# Metronome.net
KiCad netlist of a schematic drawn in Altium Designer
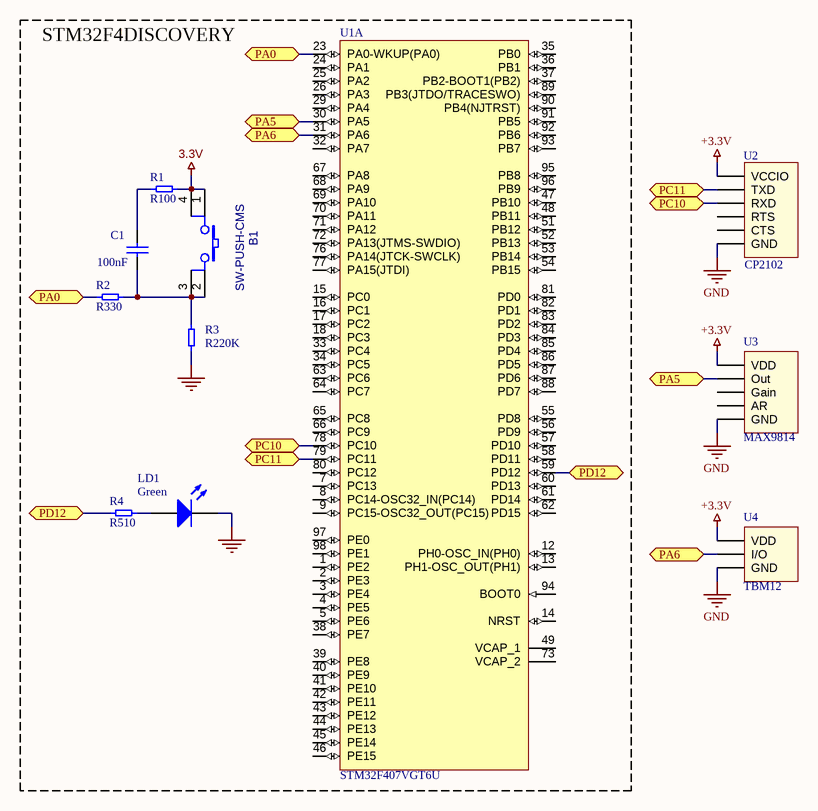
[diagram p0: Metronome.SchDoc]

(export (version "E")
  (design (tool "Eeschema 10.0.6"))
  (components
    (comp (ref "B1")
      (value "SW-PUSH-CMS")
      (footprint "BP1CMS")
      (description "Non-Open Push-Button 0.1A 24V")
      (libsource (lib "MB913_1") (part "SW-PUSH-CMS"))
    )
    (comp (ref "C1")
      (value "100nF")
      (footprint "RAD-0.3")
      (description "Capacitor")
      (fields (field (name "PUBLISHER") "Altium Limited"))
      (libsource (lib "Miscellaneous Devices") (part "Cap"))
    )
    (comp (ref "LD1")
      (value "Green")
      (footprint "3.2X1.6X1.1")
      (description "Typical RED, GREEN, YELLOW, AMBER GaAs LED")
      (fields (field (name "PUBLISHER") "Altium Limited"))
      (libsource (lib "Miscellaneous Devices") (part "LED2"))
    )
    (comp (ref "R1") (value "R100") (footprint "SMD") (libsource (lib "Metronome_components") (part "R330")))
    (comp (ref "R2") (value "R330") (footprint "SMD") (libsource (lib "Metronome_components") (part "R330")))
    (comp (ref "R3") (value "R220K") (footprint "SMD") (libsource (lib "Metronome_components") (part "R330")))
    (comp (ref "R4") (value "R510") (footprint "SMD") (libsource (lib "Metronome_components") (part "R330")))
    (comp (ref "U1")
      (value "STM32F407VGT6U")
      (footprint "STM-LQFP100_N")
      (fields (field (name "MANUFACTURER") "STMicroelectronics"))
      (libsource (lib "STMicroelectronics STM32 F4") (part "STM32F407VGT6U"))
    )
    (comp (ref "U2")
      (value "CP2102")
      (footprint "CP2102_MD")
      (description "UART-USB converter module")
      (libsource (lib "Metronome_components") (part "CP2102"))
    )
    (comp (ref "U3")
      (value "MAX9814")
      (footprint "MAX9814")
      (description "Microphone module. 3.3V - 5V. Output: 2Vpp max")
      (libsource (lib "Metronome_components") (part "MAX9814"))
    )
    (comp (ref "U4")
      (value "TBM12")
      (footprint "TBM12")
      (description "Passive buzzer. 3.3V - 5V")
      (libsource (lib "Metronome_components") (part "TBM12"))
    )
  )
  (nets
    (net (code "1") (name "+3.3V") (class "Default")
      (node (ref "U2") (pin "0") (pinfunction "VCCIO_0") (pintype "passive"))
      (node (ref "U3") (pin "0") (pinfunction "VDD_0") (pintype "power_in"))
      (node (ref "U4") (pin "0") (pinfunction "VDD_0") (pintype "power_in"))
    )
    (net (code "2") (name "/PA0") (class "Default")
      (node (ref "R2") (pin "0") (pinfunction "1_0") (pintype "passive"))
      (node (ref "U1") (pin "23") (pinfunction "PA0-WKUP(PA0)_23") (pintype "bidirectional"))
    )
    (net (code "3") (name "/PA5") (class "Default")
      (node (ref "U1") (pin "30") (pinfunction "PA5_30") (pintype "bidirectional"))
      (node (ref "U3") (pin "1") (pinfunction "Out_1") (pintype "passive"))
    )
    (net (code "4") (name "/PA6") (class "Default")
      (node (ref "U1") (pin "31") (pinfunction "PA6_31") (pintype "bidirectional"))
      (node (ref "U4") (pin "1") (pinfunction "I/O_1") (pintype "passive"))
    )
    (net (code "5") (name "/PC10") (class "Default")
      (node (ref "U1") (pin "78") (pinfunction "PC10_78") (pintype "bidirectional"))
      (node (ref "U2") (pin "2") (pinfunction "RXD_2") (pintype "passive"))
    )
    (net (code "6") (name "/PC11") (class "Default")
      (node (ref "U1") (pin "79") (pinfunction "PC11_79") (pintype "bidirectional"))
      (node (ref "U2") (pin "1") (pinfunction "TXD_1") (pintype "passive"))
    )
    (net (code "7") (name "/PD12") (class "Default")
      (node (ref "R4") (pin "0") (pinfunction "1_0") (pintype "passive"))
      (node (ref "U1") (pin "59") (pinfunction "PD12_59") (pintype "bidirectional"))
    )
    (net (code "8") (name "3.3V") (class "Default")
      (node (ref "B1") (pin "1") (pinfunction "1_1") (pintype "passive"))
      (node (ref "B1") (pin "4") (pinfunction "4_4") (pintype "passive"))
      (node (ref "R1") (pin "1") (pinfunction "2_1") (pintype "passive"))
    )
    (net (code "9") (name "GND") (class "Default")
      (node (ref "LD1") (pin "2") (pinfunction "K_2") (pintype "passive"))
      (node (ref "R3") (pin "0") (pinfunction "1_0") (pintype "passive"))
      (node (ref "U2") (pin "5") (pinfunction "GND_5") (pintype "passive"))
      (node (ref "U3") (pin "4") (pinfunction "GND_4") (pintype "passive"))
      (node (ref "U4") (pin "2") (pinfunction "GND_2") (pintype "passive"))
    )
    (net (code "10") (name "Net-(LD1-A)") (class "Default")
      (node (ref "LD1") (pin "1") (pinfunction "A_1") (pintype "passive"))
      (node (ref "R4") (pin "1") (pinfunction "2_1") (pintype "passive"))
    )
    (net (code "11") (name "Net-(R1-1)") (class "Default")
      (node (ref "C1") (pin "2") (pinfunction "2_2") (pintype "passive"))
      (node (ref "R1") (pin "0") (pinfunction "1_0") (pintype "passive"))
    )
    (net (code "12") (name "Net-(R2-2)") (class "Default")
      (node (ref "B1") (pin "2") (pinfunction "2_2") (pintype "passive"))
      (node (ref "B1") (pin "3") (pinfunction "3_3") (pintype "passive"))
      (node (ref "C1") (pin "1") (pinfunction "1_1") (pintype "passive"))
      (node (ref "R2") (pin "1") (pinfunction "2_1") (pintype "passive"))
      (node (ref "R3") (pin "1") (pinfunction "2_1") (pintype "passive"))
    )
    (net (code "13") (name "unconnected-(U1A-BOOT0-Pad94)") (class "Default")
      (node (ref "U1") (pin "94") (pinfunction "BOOT0_94") (pintype "input"))
    )
    (net (code "14") (name "unconnected-(U1A-NRST-Pad14)") (class "Default")
      (node (ref "U1") (pin "14") (pinfunction "NRST_14") (pintype "bidirectional"))
    )
    (net (code "15") (name "unconnected-(U1A-PA1-Pad24)") (class "Default")
      (node (ref "U1") (pin "24") (pinfunction "PA1_24") (pintype "bidirectional"))
    )
    (net (code "16") (name "unconnected-(U1A-PA2-Pad25)") (class "Default")
      (node (ref "U1") (pin "25") (pinfunction "PA2_25") (pintype "bidirectional"))
    )
    (net (code "17") (name "unconnected-(U1A-PA3-Pad26)") (class "Default")
      (node (ref "U1") (pin "26") (pinfunction "PA3_26") (pintype "bidirectional"))
    )
    (net (code "18") (name "unconnected-(U1A-PA4-Pad29)") (class "Default")
      (node (ref "U1") (pin "29") (pinfunction "PA4_29") (pintype "bidirectional"))
    )
    (net (code "19") (name "unconnected-(U1A-PA7-Pad32)") (class "Default")
      (node (ref "U1") (pin "32") (pinfunction "PA7_32") (pintype "bidirectional"))
    )
    (net (code "20") (name "unconnected-(U1A-PA8-Pad67)") (class "Default")
      (node (ref "U1") (pin "67") (pinfunction "PA8_67") (pintype "bidirectional"))
    )
    (net (code "21") (name "unconnected-(U1A-PA9-Pad68)") (class "Default")
      (node (ref "U1") (pin "68") (pinfunction "PA9_68") (pintype "bidirectional"))
    )
    (net (code "22") (name "unconnected-(U1A-PA10-Pad69)") (class "Default")
      (node (ref "U1") (pin "69") (pinfunction "PA10_69") (pintype "bidirectional"))
    )
    (net (code "23") (name "unconnected-(U1A-PA11-Pad70)") (class "Default")
      (node (ref "U1") (pin "70") (pinfunction "PA11_70") (pintype "bidirectional"))
    )
    (net (code "24") (name "unconnected-(U1A-PA12-Pad71)") (class "Default")
      (node (ref "U1") (pin "71") (pinfunction "PA12_71") (pintype "bidirectional"))
    )
    (net (code "25") (name "unconnected-(U1A-PA13(JTMS-SWDIO)-Pad72)") (class "Default")
      (node (ref "U1") (pin "72") (pinfunction "PA13(JTMS-SWDIO)_72") (pintype "bidirectional"))
    )
    (net (code "26") (name "unconnected-(U1A-PA14(JTCK-SWCLK)-Pad76)") (class "Default")
      (node (ref "U1") (pin "76") (pinfunction "PA14(JTCK-SWCLK)_76") (pintype "bidirectional"))
    )
    (net (code "27") (name "unconnected-(U1A-PA15(JTDI)-Pad77)") (class "Default")
      (node (ref "U1") (pin "77") (pinfunction "PA15(JTDI)_77") (pintype "bidirectional"))
    )
    (net (code "28") (name "unconnected-(U1A-PB0-Pad35)") (class "Default")
      (node (ref "U1") (pin "35") (pinfunction "PB0_35") (pintype "bidirectional"))
    )
    (net (code "29") (name "unconnected-(U1A-PB1-Pad36)") (class "Default")
      (node (ref "U1") (pin "36") (pinfunction "PB1_36") (pintype "bidirectional"))
    )
    (net (code "30") (name "unconnected-(U1A-PB2-BOOT1(PB2)-Pad37)") (class "Default")
      (node (ref "U1") (pin "37") (pinfunction "PB2-BOOT1(PB2)_37") (pintype "bidirectional"))
    )
    (net (code "31") (name "unconnected-(U1A-PB3(JTDO{slash}TRACESWO)-Pad89)") (class "Default")
      (node (ref "U1") (pin "89") (pinfunction "PB3(JTDO/TRACESWO)_89") (pintype "bidirectional"))
    )
    (net (code "32") (name "unconnected-(U1A-PB4(NJTRST)-Pad90)") (class "Default")
      (node (ref "U1") (pin "90") (pinfunction "PB4(NJTRST)_90") (pintype "bidirectional"))
    )
    (net (code "33") (name "unconnected-(U1A-PB5-Pad91)") (class "Default")
      (node (ref "U1") (pin "91") (pinfunction "PB5_91") (pintype "bidirectional"))
    )
    (net (code "34") (name "unconnected-(U1A-PB6-Pad92)") (class "Default")
      (node (ref "U1") (pin "92") (pinfunction "PB6_92") (pintype "bidirectional"))
    )
    (net (code "35") (name "unconnected-(U1A-PB7-Pad93)") (class "Default")
      (node (ref "U1") (pin "93") (pinfunction "PB7_93") (pintype "bidirectional"))
    )
    (net (code "36") (name "unconnected-(U1A-PB8-Pad95)") (class "Default")
      (node (ref "U1") (pin "95") (pinfunction "PB8_95") (pintype "bidirectional"))
    )
    (net (code "37") (name "unconnected-(U1A-PB9-Pad96)") (class "Default")
      (node (ref "U1") (pin "96") (pinfunction "PB9_96") (pintype "bidirectional"))
    )
    (net (code "38") (name "unconnected-(U1A-PB10-Pad47)") (class "Default")
      (node (ref "U1") (pin "47") (pinfunction "PB10_47") (pintype "bidirectional"))
    )
    (net (code "39") (name "unconnected-(U1A-PB11-Pad48)") (class "Default")
      (node (ref "U1") (pin "48") (pinfunction "PB11_48") (pintype "bidirectional"))
    )
    (net (code "40") (name "unconnected-(U1A-PB12-Pad51)") (class "Default")
      (node (ref "U1") (pin "51") (pinfunction "PB12_51") (pintype "bidirectional"))
    )
    (net (code "41") (name "unconnected-(U1A-PB13-Pad52)") (class "Default")
      (node (ref "U1") (pin "52") (pinfunction "PB13_52") (pintype "bidirectional"))
    )
    (net (code "42") (name "unconnected-(U1A-PB14-Pad53)") (class "Default")
      (node (ref "U1") (pin "53") (pinfunction "PB14_53") (pintype "bidirectional"))
    )
    (net (code "43") (name "unconnected-(U1A-PB15-Pad54)") (class "Default")
      (node (ref "U1") (pin "54") (pinfunction "PB15_54") (pintype "bidirectional"))
    )
    (net (code "44") (name "unconnected-(U1A-PC0-Pad15)") (class "Default")
      (node (ref "U1") (pin "15") (pinfunction "PC0_15") (pintype "bidirectional"))
    )
    (net (code "45") (name "unconnected-(U1A-PC1-Pad16)") (class "Default")
      (node (ref "U1") (pin "16") (pinfunction "PC1_16") (pintype "bidirectional"))
    )
    (net (code "46") (name "unconnected-(U1A-PC2-Pad17)") (class "Default")
      (node (ref "U1") (pin "17") (pinfunction "PC2_17") (pintype "bidirectional"))
    )
    (net (code "47") (name "unconnected-(U1A-PC3-Pad18)") (class "Default")
      (node (ref "U1") (pin "18") (pinfunction "PC3_18") (pintype "bidirectional"))
    )
    (net (code "48") (name "unconnected-(U1A-PC4-Pad33)") (class "Default")
      (node (ref "U1") (pin "33") (pinfunction "PC4_33") (pintype "bidirectional"))
    )
    (net (code "49") (name "unconnected-(U1A-PC5-Pad34)") (class "Default")
      (node (ref "U1") (pin "34") (pinfunction "PC5_34") (pintype "bidirectional"))
    )
    (net (code "50") (name "unconnected-(U1A-PC6-Pad63)") (class "Default")
      (node (ref "U1") (pin "63") (pinfunction "PC6_63") (pintype "bidirectional"))
    )
    (net (code "51") (name "unconnected-(U1A-PC7-Pad64)") (class "Default")
      (node (ref "U1") (pin "64") (pinfunction "PC7_64") (pintype "bidirectional"))
    )
    (net (code "52") (name "unconnected-(U1A-PC8-Pad65)") (class "Default")
      (node (ref "U1") (pin "65") (pinfunction "PC8_65") (pintype "bidirectional"))
    )
    (net (code "53") (name "unconnected-(U1A-PC9-Pad66)") (class "Default")
      (node (ref "U1") (pin "66") (pinfunction "PC9_66") (pintype "bidirectional"))
    )
    (net (code "54") (name "unconnected-(U1A-PC12-Pad80)") (class "Default")
      (node (ref "U1") (pin "80") (pinfunction "PC12_80") (pintype "bidirectional"))
    )
    (net (code "55") (name "unconnected-(U1A-PC13-Pad7)") (class "Default")
      (node (ref "U1") (pin "7") (pinfunction "PC13_7") (pintype "bidirectional"))
    )
    (net (code "56") (name "unconnected-(U1A-PC14-OSC32_IN(PC14)-Pad8)") (class "Default")
      (node (ref "U1") (pin "8") (pinfunction "PC14-OSC32_IN(PC14)_8") (pintype "bidirectional"))
    )
    (net (code "57") (name "unconnected-(U1A-PC15-OSC32_OUT(PC15)-Pad9)") (class "Default")
      (node (ref "U1") (pin "9") (pinfunction "PC15-OSC32_OUT(PC15)_9") (pintype "bidirectional"))
    )
    (net (code "58") (name "unconnected-(U1A-PD0-Pad81)") (class "Default")
      (node (ref "U1") (pin "81") (pinfunction "PD0_81") (pintype "bidirectional"))
    )
    (net (code "59") (name "unconnected-(U1A-PD1-Pad82)") (class "Default")
      (node (ref "U1") (pin "82") (pinfunction "PD1_82") (pintype "bidirectional"))
    )
    (net (code "60") (name "unconnected-(U1A-PD2-Pad83)") (class "Default")
      (node (ref "U1") (pin "83") (pinfunction "PD2_83") (pintype "bidirectional"))
    )
    (net (code "61") (name "unconnected-(U1A-PD3-Pad84)") (class "Default")
      (node (ref "U1") (pin "84") (pinfunction "PD3_84") (pintype "bidirectional"))
    )
    (net (code "62") (name "unconnected-(U1A-PD4-Pad85)") (class "Default")
      (node (ref "U1") (pin "85") (pinfunction "PD4_85") (pintype "bidirectional"))
    )
    (net (code "63") (name "unconnected-(U1A-PD5-Pad86)") (class "Default")
      (node (ref "U1") (pin "86") (pinfunction "PD5_86") (pintype "bidirectional"))
    )
    (net (code "64") (name "unconnected-(U1A-PD6-Pad87)") (class "Default")
      (node (ref "U1") (pin "87") (pinfunction "PD6_87") (pintype "bidirectional"))
    )
    (net (code "65") (name "unconnected-(U1A-PD7-Pad88)") (class "Default")
      (node (ref "U1") (pin "88") (pinfunction "PD7_88") (pintype "bidirectional"))
    )
    (net (code "66") (name "unconnected-(U1A-PD8-Pad55)") (class "Default")
      (node (ref "U1") (pin "55") (pinfunction "PD8_55") (pintype "bidirectional"))
    )
    (net (code "67") (name "unconnected-(U1A-PD9-Pad56)") (class "Default")
      (node (ref "U1") (pin "56") (pinfunction "PD9_56") (pintype "bidirectional"))
    )
    (net (code "68") (name "unconnected-(U1A-PD10-Pad57)") (class "Default")
      (node (ref "U1") (pin "57") (pinfunction "PD10_57") (pintype "bidirectional"))
    )
    (net (code "69") (name "unconnected-(U1A-PD11-Pad58)") (class "Default")
      (node (ref "U1") (pin "58") (pinfunction "PD11_58") (pintype "bidirectional"))
    )
    (net (code "70") (name "unconnected-(U1A-PD13-Pad60)") (class "Default")
      (node (ref "U1") (pin "60") (pinfunction "PD13_60") (pintype "bidirectional"))
    )
    (net (code "71") (name "unconnected-(U1A-PD14-Pad61)") (class "Default")
      (node (ref "U1") (pin "61") (pinfunction "PD14_61") (pintype "bidirectional"))
    )
    (net (code "72") (name "unconnected-(U1A-PD15-Pad62)") (class "Default")
      (node (ref "U1") (pin "62") (pinfunction "PD15_62") (pintype "bidirectional"))
    )
    (net (code "73") (name "unconnected-(U1A-PE0-Pad97)") (class "Default")
      (node (ref "U1") (pin "97") (pinfunction "PE0_97") (pintype "bidirectional"))
    )
    (net (code "74") (name "unconnected-(U1A-PE1-Pad98)") (class "Default")
      (node (ref "U1") (pin "98") (pinfunction "PE1_98") (pintype "bidirectional"))
    )
    (net (code "75") (name "unconnected-(U1A-PE2-Pad1)") (class "Default")
      (node (ref "U1") (pin "1") (pinfunction "PE2_1") (pintype "bidirectional"))
    )
    (net (code "76") (name "unconnected-(U1A-PE3-Pad2)") (class "Default")
      (node (ref "U1") (pin "2") (pinfunction "PE3_2") (pintype "bidirectional"))
    )
    (net (code "77") (name "unconnected-(U1A-PE4-Pad3)") (class "Default")
      (node (ref "U1") (pin "3") (pinfunction "PE4_3") (pintype "bidirectional"))
    )
    (net (code "78") (name "unconnected-(U1A-PE5-Pad4)") (class "Default")
      (node (ref "U1") (pin "4") (pinfunction "PE5_4") (pintype "bidirectional"))
    )
    (net (code "79") (name "unconnected-(U1A-PE6-Pad5)") (class "Default")
      (node (ref "U1") (pin "5") (pinfunction "PE6_5") (pintype "bidirectional"))
    )
    (net (code "80") (name "unconnected-(U1A-PE7-Pad38)") (class "Default")
      (node (ref "U1") (pin "38") (pinfunction "PE7_38") (pintype "bidirectional"))
    )
    (net (code "81") (name "unconnected-(U1A-PE8-Pad39)") (class "Default")
      (node (ref "U1") (pin "39") (pinfunction "PE8_39") (pintype "bidirectional"))
    )
    (net (code "82") (name "unconnected-(U1A-PE9-Pad40)") (class "Default")
      (node (ref "U1") (pin "40") (pinfunction "PE9_40") (pintype "bidirectional"))
    )
    (net (code "83") (name "unconnected-(U1A-PE10-Pad41)") (class "Default")
      (node (ref "U1") (pin "41") (pinfunction "PE10_41") (pintype "bidirectional"))
    )
    (net (code "84") (name "unconnected-(U1A-PE11-Pad42)") (class "Default")
      (node (ref "U1") (pin "42") (pinfunction "PE11_42") (pintype "bidirectional"))
    )
    (net (code "85") (name "unconnected-(U1A-PE12-Pad43)") (class "Default")
      (node (ref "U1") (pin "43") (pinfunction "PE12_43") (pintype "bidirectional"))
    )
    (net (code "86") (name "unconnected-(U1A-PE13-Pad44)") (class "Default")
      (node (ref "U1") (pin "44") (pinfunction "PE13_44") (pintype "bidirectional"))
    )
    (net (code "87") (name "unconnected-(U1A-PE14-Pad45)") (class "Default")
      (node (ref "U1") (pin "45") (pinfunction "PE14_45") (pintype "bidirectional"))
    )
    (net (code "88") (name "unconnected-(U1A-PE15-Pad46)") (class "Default")
      (node (ref "U1") (pin "46") (pinfunction "PE15_46") (pintype "bidirectional"))
    )
    (net (code "89") (name "unconnected-(U1A-PH0-OSC_IN(PH0)-Pad12)") (class "Default")
      (node (ref "U1") (pin "12") (pinfunction "PH0-OSC_IN(PH0)_12") (pintype "bidirectional"))
    )
    (net (code "90") (name "unconnected-(U1A-PH1-OSC_OUT(PH1)-Pad13)") (class "Default")
      (node (ref "U1") (pin "13") (pinfunction "PH1-OSC_OUT(PH1)_13") (pintype "bidirectional"))
    )
    (net (code "91") (name "unconnected-(U1A-VCAP_1-Pad49)") (class "Default")
      (node (ref "U1") (pin "49") (pinfunction "VCAP_1_49") (pintype "power_in"))
    )
    (net (code "92") (name "unconnected-(U1A-VCAP_2-Pad73)") (class "Default")
      (node (ref "U1") (pin "73") (pinfunction "VCAP_2_73") (pintype "power_in"))
    )
    (net (code "93") (name "unconnected-(U2-CTS-Pad4)") (class "Default")
      (node (ref "U2") (pin "4") (pinfunction "CTS_4") (pintype "passive"))
    )
    (net (code "94") (name "unconnected-(U2-RTS-Pad3)") (class "Default")
      (node (ref "U2") (pin "3") (pinfunction "RTS_3") (pintype "passive"))
    )
    (net (code "95") (name "unconnected-(U3-AR-Pad3)") (class "Default")
      (node (ref "U3") (pin "3") (pinfunction "AR_3") (pintype "passive"))
    )
    (net (code "96") (name "unconnected-(U3-Gain-Pad2)") (class "Default")
      (node (ref "U3") (pin "2") (pinfunction "Gain_2") (pintype "power_in"))
    )
  )
)
